# Pixel8x4U.net
KiCad netlist of a schematic drawn in EAGLE
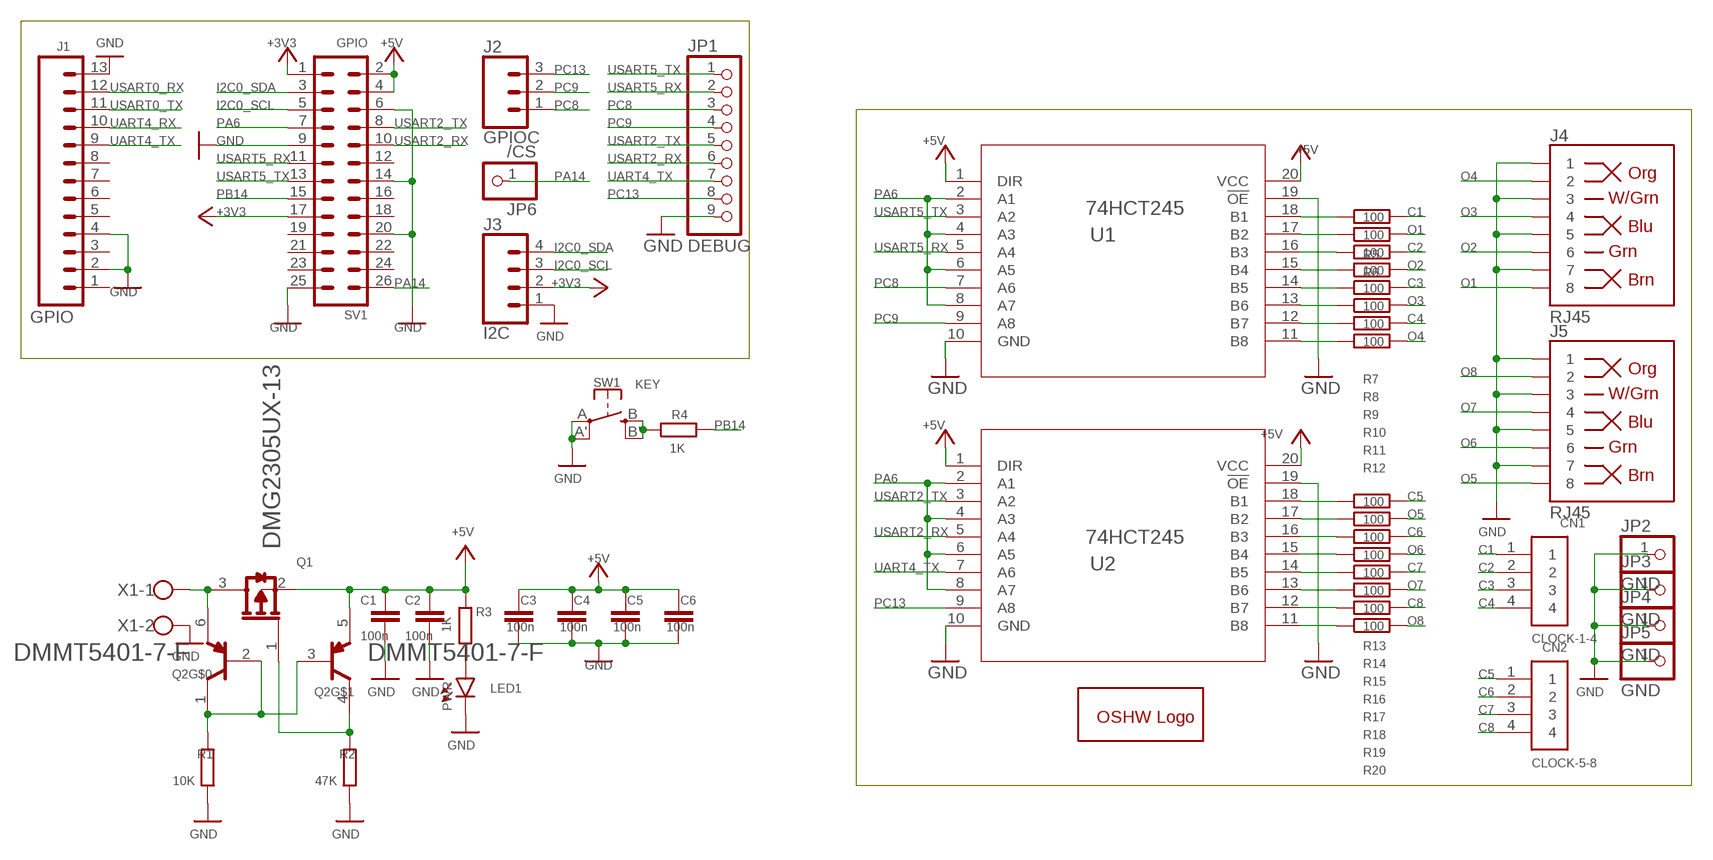
[diagram p0: schematic, sheet 1]

(export (version "E")
  (design (tool "Eeschema 10.0.6"))
  (components
    (comp (ref "C1")
      (value "100n")
      (footprint "eagle-import:C0603")
      (libsource (lib "eagle-import") (part "C-EUC0603"))
    )
    (comp (ref "C2")
      (value "100n")
      (footprint "eagle-import:C0603")
      (libsource (lib "eagle-import") (part "C-EUC0603"))
    )
    (comp (ref "C3")
      (value "100n")
      (footprint "eagle-import:C0603")
      (libsource (lib "eagle-import") (part "C-EUC0603"))
    )
    (comp (ref "C4")
      (value "100n")
      (footprint "eagle-import:C0603")
      (libsource (lib "eagle-import") (part "C-EUC0603"))
    )
    (comp (ref "C5")
      (value "100n")
      (footprint "eagle-import:C0603")
      (libsource (lib "eagle-import") (part "C-EUC0603"))
    )
    (comp (ref "C6")
      (value "100n")
      (footprint "eagle-import:C0603")
      (libsource (lib "eagle-import") (part "C-EUC0603"))
    )
    (comp (ref "CN1")
      (value "CLOCK-1-4")
      (footprint "eagle-import:1X04-CLEANBIG")
      (libsource (lib "eagle-import") (part "1X4-CLEANBIG"))
    )
    (comp (ref "CN2")
      (value "CLOCK-5-8")
      (footprint "eagle-import:1X04-CLEANBIG")
      (libsource (lib "eagle-import") (part "1X4-CLEANBIG"))
    )
    (comp (ref "GOLD_ORB_SM1")
      (value "OSHWLOGOLOGO5MM")
      (footprint "eagle-import:OSHW_5MM")
      (libsource (lib "eagle-import") (part "OSHWLOGOLOGO5MM"))
    )
    (comp (ref "J1")
      (value "GPIO")
      (footprint "eagle-import:1X13")
      (libsource (lib "eagle-import") (part "CONN_13"))
    )
    (comp (ref "J2")
      (value "GPIOC")
      (footprint "eagle-import:1X03")
      (libsource (lib "eagle-import") (part "CONN_03"))
    )
    (comp (ref "J3")
      (value "I2C")
      (footprint "eagle-import:1X04")
      (libsource (lib "eagle-import") (part "CONN_04"))
    )
    (comp (ref "J4")
      (value "RJ45")
      (footprint "eagle-import:RJ45-8")
      (libsource (lib "eagle-import") (part "RJ45-8"))
    )
    (comp (ref "J5")
      (value "RJ45")
      (footprint "eagle-import:RJ45-8")
      (libsource (lib "eagle-import") (part "RJ45-8"))
    )
    (comp (ref "JP1")
      (value "DEBUG")
      (footprint "eagle-import:1X09")
      (libsource (lib "eagle-import") (part "PINHD-1X9"))
    )
    (comp (ref "JP2")
      (value "GND")
      (footprint "eagle-import:1X01-CLEANBIG")
      (libsource (lib "eagle-import") (part "PINHD-1X1CB"))
    )
    (comp (ref "JP3")
      (value "GND")
      (footprint "eagle-import:1X01-CLEANBIG")
      (libsource (lib "eagle-import") (part "PINHD-1X1CB"))
    )
    (comp (ref "JP4")
      (value "GND")
      (footprint "eagle-import:1X01-CLEANBIG")
      (libsource (lib "eagle-import") (part "PINHD-1X1CB"))
    )
    (comp (ref "JP5")
      (value "GND")
      (footprint "eagle-import:1X01-CLEANBIG")
      (libsource (lib "eagle-import") (part "PINHD-1X1CB"))
    )
    (comp (ref "JP6")
      (value "/CS")
      (footprint "eagle-import:1X01-CLEANBIG")
      (libsource (lib "eagle-import") (part "PINHD-1X1CB"))
    )
    (comp (ref "LED1")
      (value "PWR")
      (footprint "eagle-import:CHIP-LED0603")
      (libsource (lib "eagle-import") (part "LEDCHIP-LED0603"))
    )
    (comp (ref "Q1")
      (value "DIODES_INC._DMG2305UX-13DIODES_INC._DMG2305UX-13_0_0")
      (footprint "eagle-import:DIODES_INC._DMG2305UX-13_0")
      (fields
        (field (name "DIGIKEY_PART_NUMBER") "DMG2305UX-13DICT-ND")
        (field (name "MF") "Diodes Inc.")
        (field (name "MOUSER_PART_NUMBER") "621-DMG2305UX-13")
      )
      (libsource (lib "eagle-import") (part "DIODES_INC._DMG2305UX-13DIODES_INC._DMG2305UX-13_0_0"))
    )
    (comp (ref "Q2")
      (value "DMMT5401-7-F_0_0")
      (footprint "eagle-import:DIODES_DMMT5401-7-F_0")
      (fields
        (field (name "DIGIKEY_PART_NUMBER") "DMMT5401-FDICT-ND")
        (field (name "MF") "Diodes")
        (field (name "MOUSER_PART_NUMBER") "621-DMMT5401-7-F")
      )
      (libsource (lib "eagle-import") (part "DIODES_DMMT5401-7-FDIODES_DMMT5401-7-F_0_0"))
    )
    (comp (ref "R1")
      (value "10K")
      (footprint "eagle-import:R0402")
      (libsource (lib "eagle-import") (part "R-EU_R0402"))
    )
    (comp (ref "R2")
      (value "47K")
      (footprint "eagle-import:R0402")
      (libsource (lib "eagle-import") (part "R-EU_R0402"))
    )
    (comp (ref "R3")
      (value "1K")
      (footprint "eagle-import:R0402")
      (libsource (lib "eagle-import") (part "resistor_348_R-EU_R0402"))
    )
    (comp (ref "R4")
      (value "1K")
      (footprint "eagle-import:R0402")
      (libsource (lib "eagle-import") (part "resistor_348_R-EU_R0402"))
    )
    (comp (ref "R5")
      (value "100")
      (footprint "eagle-import:R0402")
      (libsource (lib "eagle-import") (part "R-EU_R0402"))
    )
    (comp (ref "R6")
      (value "100")
      (footprint "eagle-import:R0402")
      (libsource (lib "eagle-import") (part "R-EU_R0402"))
    )
    (comp (ref "R7")
      (value "100")
      (footprint "eagle-import:R0402")
      (libsource (lib "eagle-import") (part "R-EU_R0402"))
    )
    (comp (ref "R8")
      (value "100")
      (footprint "eagle-import:R0402")
      (libsource (lib "eagle-import") (part "R-EU_R0402"))
    )
    (comp (ref "R9")
      (value "100")
      (footprint "eagle-import:R0402")
      (libsource (lib "eagle-import") (part "R-EU_R0402"))
    )
    (comp (ref "R10")
      (value "100")
      (footprint "eagle-import:R0402")
      (libsource (lib "eagle-import") (part "R-EU_R0402"))
    )
    (comp (ref "R11")
      (value "100")
      (footprint "eagle-import:R0402")
      (libsource (lib "eagle-import") (part "R-EU_R0402"))
    )
    (comp (ref "R12")
      (value "100")
      (footprint "eagle-import:R0402")
      (libsource (lib "eagle-import") (part "R-EU_R0402"))
    )
    (comp (ref "R13")
      (value "100")
      (footprint "eagle-import:R0402")
      (libsource (lib "eagle-import") (part "R-EU_R0402"))
    )
    (comp (ref "R14")
      (value "100")
      (footprint "eagle-import:R0402")
      (libsource (lib "eagle-import") (part "R-EU_R0402"))
    )
    (comp (ref "R15")
      (value "100")
      (footprint "eagle-import:R0402")
      (libsource (lib "eagle-import") (part "R-EU_R0402"))
    )
    (comp (ref "R16")
      (value "100")
      (footprint "eagle-import:R0402")
      (libsource (lib "eagle-import") (part "R-EU_R0402"))
    )
    (comp (ref "R17")
      (value "100")
      (footprint "eagle-import:R0402")
      (libsource (lib "eagle-import") (part "R-EU_R0402"))
    )
    (comp (ref "R18")
      (value "100")
      (footprint "eagle-import:R0402")
      (libsource (lib "eagle-import") (part "R-EU_R0402"))
    )
    (comp (ref "R19")
      (value "100")
      (footprint "eagle-import:R0402")
      (libsource (lib "eagle-import") (part "R-EU_R0402"))
    )
    (comp (ref "R20")
      (value "100")
      (footprint "eagle-import:R0402")
      (libsource (lib "eagle-import") (part "R-EU_R0402"))
    )
    (comp (ref "SV1")
      (value "GPIO")
      (footprint "eagle-import:MA13-2")
      (libsource (lib "eagle-import") (part "MA13-2"))
    )
    (comp (ref "SW1")
      (value "KEY")
      (footprint "eagle-import:EVQ-Q2")
      (libsource (lib "eagle-import") (part "SPST_TACT-EVQQ2"))
    )
    (comp (ref "U1")
      (value "74HCT245")
      (footprint "eagle-import:PW20")
      (fields
        (field (name "GENERIC_PART_NUMBER") "SN74HCT245")
        (field (name "MANUFACTURER") "Texas Instruments")
        (field (name "MANUFACTURER_PART_NUMBER") "SN74HCT245PWR")
      )
      (libsource (lib "eagle-import") (part "SN74HCT245PWR"))
    )
    (comp (ref "U2")
      (value "74HCT245")
      (footprint "eagle-import:PW20")
      (fields
        (field (name "GENERIC_PART_NUMBER") "SN74HCT245")
        (field (name "MANUFACTURER") "Texas Instruments")
        (field (name "MANUFACTURER_PART_NUMBER") "SN74HCT245PWR")
      )
      (libsource (lib "eagle-import") (part "SN74HCT245PWR"))
    )
    (comp (ref "X1")
      (value "W237-102")
      (footprint "eagle-import:W237-102")
      (fields (field (name "MPN") "237-102"))
      (libsource (lib "eagle-import") (part "W237-102"))
    )
  )
  (nets
    (net (code "1") (name "+3V3") (class "Default")
      (node (ref "J3") (pin "2") (pinfunction "2_2") (pintype "passive"))
      (node (ref "SV1") (pin "1") (pinfunction "1_1") (pintype "passive"))
      (node (ref "SV1") (pin "17") (pinfunction "17_17") (pintype "passive"))
    )
    (net (code "2") (name "+5V") (class "Default")
      (node (ref "C1") (pin "1") (pinfunction "1_1") (pintype "passive"))
      (node (ref "C2") (pin "1") (pinfunction "1_1") (pintype "passive"))
      (node (ref "C3") (pin "1") (pinfunction "1_1") (pintype "passive"))
      (node (ref "C4") (pin "1") (pinfunction "1_1") (pintype "passive"))
      (node (ref "C5") (pin "1") (pinfunction "1_1") (pintype "passive"))
      (node (ref "C6") (pin "1") (pinfunction "1_1") (pintype "passive"))
      (node (ref "Q1") (pin "2") (pinfunction "S_2") (pintype "passive"))
      (node (ref "Q2") (pin "5") (pinfunction "E2_5") (pintype "passive"))
      (node (ref "R3") (pin "1") (pinfunction "1_1") (pintype "passive"))
      (node (ref "SV1") (pin "2") (pinfunction "2_2") (pintype "passive"))
      (node (ref "SV1") (pin "4") (pinfunction "4_4") (pintype "passive"))
      (node (ref "U1") (pin "1") (pinfunction "DIR_1") (pintype "input"))
      (node (ref "U1") (pin "20") (pinfunction "VCC_20") (pintype "power_in"))
      (node (ref "U2") (pin "1") (pinfunction "DIR_1") (pintype "input"))
      (node (ref "U2") (pin "20") (pinfunction "VCC_20") (pintype "power_in"))
    )
    (net (code "3") (name "/C1") (class "Default")
      (node (ref "CN1") (pin "1") (pinfunction "1_1") (pintype "bidirectional"))
      (node (ref "R5") (pin "2") (pinfunction "2_2") (pintype "passive"))
    )
    (net (code "4") (name "/C2") (class "Default")
      (node (ref "CN1") (pin "2") (pinfunction "2_2") (pintype "bidirectional"))
      (node (ref "R7") (pin "2") (pinfunction "2_2") (pintype "passive"))
    )
    (net (code "5") (name "/C3") (class "Default")
      (node (ref "CN1") (pin "3") (pinfunction "3_3") (pintype "bidirectional"))
      (node (ref "R9") (pin "2") (pinfunction "2_2") (pintype "passive"))
    )
    (net (code "6") (name "/C4") (class "Default")
      (node (ref "CN1") (pin "4") (pinfunction "4_4") (pintype "bidirectional"))
      (node (ref "R11") (pin "2") (pinfunction "2_2") (pintype "passive"))
    )
    (net (code "7") (name "/C5") (class "Default")
      (node (ref "CN2") (pin "1") (pinfunction "1_1") (pintype "bidirectional"))
      (node (ref "R13") (pin "2") (pinfunction "2_2") (pintype "passive"))
    )
    (net (code "8") (name "/C6") (class "Default")
      (node (ref "CN2") (pin "2") (pinfunction "2_2") (pintype "bidirectional"))
      (node (ref "R15") (pin "2") (pinfunction "2_2") (pintype "passive"))
    )
    (net (code "9") (name "/C7") (class "Default")
      (node (ref "CN2") (pin "3") (pinfunction "3_3") (pintype "bidirectional"))
      (node (ref "R17") (pin "2") (pinfunction "2_2") (pintype "passive"))
    )
    (net (code "10") (name "/C8") (class "Default")
      (node (ref "CN2") (pin "4") (pinfunction "4_4") (pintype "bidirectional"))
      (node (ref "R19") (pin "2") (pinfunction "2_2") (pintype "passive"))
    )
    (net (code "11") (name "/I2C0_SCL") (class "Default")
      (node (ref "J3") (pin "3") (pinfunction "3_3") (pintype "passive"))
      (node (ref "SV1") (pin "5") (pinfunction "5_5") (pintype "passive"))
    )
    (net (code "12") (name "/I2C0_SDA") (class "Default")
      (node (ref "J3") (pin "4") (pinfunction "4_4") (pintype "passive"))
      (node (ref "SV1") (pin "3") (pinfunction "3_3") (pintype "passive"))
    )
    (net (code "13") (name "/O1") (class "Default")
      (node (ref "J4") (pin "8") (pinfunction "8_8") (pintype "bidirectional"))
      (node (ref "R6") (pin "2") (pinfunction "2_2") (pintype "passive"))
    )
    (net (code "14") (name "/O2") (class "Default")
      (node (ref "J4") (pin "6") (pinfunction "6_6") (pintype "bidirectional"))
      (node (ref "R8") (pin "2") (pinfunction "2_2") (pintype "passive"))
    )
    (net (code "15") (name "/O3") (class "Default")
      (node (ref "J4") (pin "4") (pinfunction "4_4") (pintype "bidirectional"))
      (node (ref "R10") (pin "2") (pinfunction "2_2") (pintype "passive"))
    )
    (net (code "16") (name "/O4") (class "Default")
      (node (ref "J4") (pin "2") (pinfunction "2_2") (pintype "bidirectional"))
      (node (ref "R12") (pin "2") (pinfunction "2_2") (pintype "passive"))
    )
    (net (code "17") (name "/O5") (class "Default")
      (node (ref "J5") (pin "8") (pinfunction "8_8") (pintype "bidirectional"))
      (node (ref "R14") (pin "2") (pinfunction "2_2") (pintype "passive"))
    )
    (net (code "18") (name "/O6") (class "Default")
      (node (ref "J5") (pin "6") (pinfunction "6_6") (pintype "bidirectional"))
      (node (ref "R16") (pin "2") (pinfunction "2_2") (pintype "passive"))
    )
    (net (code "19") (name "/O7") (class "Default")
      (node (ref "J5") (pin "4") (pinfunction "4_4") (pintype "bidirectional"))
      (node (ref "R18") (pin "2") (pinfunction "2_2") (pintype "passive"))
    )
    (net (code "20") (name "/O8") (class "Default")
      (node (ref "J5") (pin "2") (pinfunction "2_2") (pintype "bidirectional"))
      (node (ref "R20") (pin "2") (pinfunction "2_2") (pintype "passive"))
    )
    (net (code "21") (name "/PA6") (class "Default")
      (node (ref "SV1") (pin "7") (pinfunction "7_7") (pintype "passive"))
      (node (ref "U1") (pin "2") (pinfunction "A1_2") (pintype "bidirectional"))
      (node (ref "U1") (pin "4") (pinfunction "A3_4") (pintype "bidirectional"))
      (node (ref "U1") (pin "6") (pinfunction "A5_6") (pintype "bidirectional"))
      (node (ref "U1") (pin "8") (pinfunction "A7_8") (pintype "bidirectional"))
      (node (ref "U2") (pin "2") (pinfunction "A1_2") (pintype "bidirectional"))
      (node (ref "U2") (pin "4") (pinfunction "A3_4") (pintype "bidirectional"))
      (node (ref "U2") (pin "6") (pinfunction "A5_6") (pintype "bidirectional"))
      (node (ref "U2") (pin "8") (pinfunction "A7_8") (pintype "bidirectional"))
    )
    (net (code "22") (name "/PA14") (class "Default")
      (node (ref "JP6") (pin "1") (pinfunction "1_1") (pintype "passive"))
      (node (ref "SV1") (pin "26") (pinfunction "26_26") (pintype "passive"))
    )
    (net (code "23") (name "/PB14") (class "Default")
      (node (ref "R4") (pin "2") (pinfunction "2_2") (pintype "passive"))
      (node (ref "SV1") (pin "15") (pinfunction "15_15") (pintype "passive"))
    )
    (net (code "24") (name "/PC8") (class "Default")
      (node (ref "J2") (pin "1") (pinfunction "1_1") (pintype "passive"))
      (node (ref "JP1") (pin "3") (pinfunction "3_3") (pintype "passive"))
      (node (ref "U1") (pin "7") (pinfunction "A6_7") (pintype "bidirectional"))
    )
    (net (code "25") (name "/PC9") (class "Default")
      (node (ref "J2") (pin "2") (pinfunction "2_2") (pintype "passive"))
      (node (ref "JP1") (pin "4") (pinfunction "4_4") (pintype "passive"))
      (node (ref "U1") (pin "9") (pinfunction "A8_9") (pintype "bidirectional"))
    )
    (net (code "26") (name "/PC13") (class "Default")
      (node (ref "J2") (pin "3") (pinfunction "3_3") (pintype "passive"))
      (node (ref "JP1") (pin "8") (pinfunction "8_8") (pintype "passive"))
      (node (ref "U2") (pin "9") (pinfunction "A8_9") (pintype "bidirectional"))
    )
    (net (code "27") (name "/UART4_RX") (class "Default")
      (node (ref "J1") (pin "10") (pinfunction "10_10") (pintype "passive"))
    )
    (net (code "28") (name "/UART4_TX") (class "Default")
      (node (ref "J1") (pin "9") (pinfunction "9_9") (pintype "passive"))
      (node (ref "JP1") (pin "7") (pinfunction "7_7") (pintype "passive"))
      (node (ref "U2") (pin "7") (pinfunction "A6_7") (pintype "bidirectional"))
    )
    (net (code "29") (name "/USART0_RX") (class "Default")
      (node (ref "J1") (pin "12") (pinfunction "12_12") (pintype "passive"))
    )
    (net (code "30") (name "/USART0_TX") (class "Default")
      (node (ref "J1") (pin "11") (pinfunction "11_11") (pintype "passive"))
    )
    (net (code "31") (name "/USART2_RX") (class "Default")
      (node (ref "JP1") (pin "6") (pinfunction "6_6") (pintype "passive"))
      (node (ref "SV1") (pin "10") (pinfunction "10_10") (pintype "passive"))
      (node (ref "U2") (pin "5") (pinfunction "A4_5") (pintype "bidirectional"))
    )
    (net (code "32") (name "/USART2_TX") (class "Default")
      (node (ref "JP1") (pin "5") (pinfunction "5_5") (pintype "passive"))
      (node (ref "SV1") (pin "8") (pinfunction "8_8") (pintype "passive"))
      (node (ref "U2") (pin "3") (pinfunction "A2_3") (pintype "bidirectional"))
    )
    (net (code "33") (name "/USART5_RX") (class "Default")
      (node (ref "JP1") (pin "2") (pinfunction "2_2") (pintype "passive"))
      (node (ref "SV1") (pin "11") (pinfunction "11_11") (pintype "passive"))
      (node (ref "U1") (pin "5") (pinfunction "A4_5") (pintype "bidirectional"))
    )
    (net (code "34") (name "/USART5_TX") (class "Default")
      (node (ref "JP1") (pin "1") (pinfunction "1_1") (pintype "passive"))
      (node (ref "SV1") (pin "13") (pinfunction "13_13") (pintype "passive"))
      (node (ref "U1") (pin "3") (pinfunction "A2_3") (pintype "bidirectional"))
    )
    (net (code "35") (name "GND") (class "Default")
      (node (ref "C1") (pin "2") (pinfunction "2_2") (pintype "passive"))
      (node (ref "C2") (pin "2") (pinfunction "2_2") (pintype "passive"))
      (node (ref "C3") (pin "2") (pinfunction "2_2") (pintype "passive"))
      (node (ref "C4") (pin "2") (pinfunction "2_2") (pintype "passive"))
      (node (ref "C5") (pin "2") (pinfunction "2_2") (pintype "passive"))
      (node (ref "C6") (pin "2") (pinfunction "2_2") (pintype "passive"))
      (node (ref "J1") (pin "13") (pinfunction "13_13") (pintype "passive"))
      (node (ref "J1") (pin "2") (pinfunction "2_2") (pintype "passive"))
      (node (ref "J1") (pin "4") (pinfunction "4_4") (pintype "passive"))
      (node (ref "J3") (pin "1") (pinfunction "1_1") (pintype "passive"))
      (node (ref "J4") (pin "1") (pinfunction "1_1") (pintype "bidirectional"))
      (node (ref "J4") (pin "3") (pinfunction "3_3") (pintype "bidirectional"))
      (node (ref "J4") (pin "5") (pinfunction "5_5") (pintype "bidirectional"))
      (node (ref "J4") (pin "7") (pinfunction "7_7") (pintype "bidirectional"))
      (node (ref "J5") (pin "1") (pinfunction "1_1") (pintype "bidirectional"))
      (node (ref "J5") (pin "3") (pinfunction "3_3") (pintype "bidirectional"))
      (node (ref "J5") (pin "5") (pinfunction "5_5") (pintype "bidirectional"))
      (node (ref "J5") (pin "7") (pinfunction "7_7") (pintype "bidirectional"))
      (node (ref "JP1") (pin "9") (pinfunction "9_9") (pintype "passive"))
      (node (ref "JP2") (pin "1") (pinfunction "1_1") (pintype "passive"))
      (node (ref "JP3") (pin "1") (pinfunction "1_1") (pintype "passive"))
      (node (ref "JP4") (pin "1") (pinfunction "1_1") (pintype "passive"))
      (node (ref "JP5") (pin "1") (pinfunction "1_1") (pintype "passive"))
      (node (ref "LED1") (pin "C") (pinfunction "C_C") (pintype "passive"))
      (node (ref "R1") (pin "1") (pinfunction "1_1") (pintype "passive"))
      (node (ref "R2") (pin "1") (pinfunction "1_1") (pintype "passive"))
      (node (ref "SV1") (pin "14") (pinfunction "14_14") (pintype "passive"))
      (node (ref "SV1") (pin "20") (pinfunction "20_20") (pintype "passive"))
      (node (ref "SV1") (pin "25") (pinfunction "25_25") (pintype "passive"))
      (node (ref "SV1") (pin "6") (pinfunction "6_6") (pintype "passive"))
      (node (ref "SV1") (pin "9") (pinfunction "9_9") (pintype "passive"))
      (node (ref "SW1") (pin "A") (pinfunction "P_A") (pintype "passive"))
      (node (ref "SW1") (pin "A'") (pinfunction "P1_A'") (pintype "passive"))
      (node (ref "U1") (pin "10") (pinfunction "GND_10") (pintype "power_in"))
      (node (ref "U1") (pin "19") (pinfunction "~{OE}_19") (pintype "input"))
      (node (ref "U2") (pin "10") (pinfunction "GND_10") (pintype "power_in"))
      (node (ref "U2") (pin "19") (pinfunction "~{OE}_19") (pintype "input"))
      (node (ref "X1") (pin "2") (pinfunction "KL_2") (pintype "passive"))
    )
    (net (code "36") (name "Net-(LED1-PadA)") (class "Default")
      (node (ref "LED1") (pin "A") (pinfunction "A_A") (pintype "passive"))
      (node (ref "R3") (pin "2") (pinfunction "2_2") (pintype "passive"))
    )
    (net (code "37") (name "Net-(Q1-D)") (class "Default")
      (node (ref "Q1") (pin "3") (pinfunction "D_3") (pintype "passive"))
      (node (ref "Q2") (pin "6") (pinfunction "E1_6") (pintype "passive"))
      (node (ref "X1") (pin "1") (pinfunction "KL_1") (pintype "passive"))
    )
    (net (code "38") (name "Net-(Q1-G)") (class "Default")
      (node (ref "Q1") (pin "1") (pinfunction "G_1") (pintype "passive"))
      (node (ref "Q2") (pin "4") (pinfunction "C2_4") (pintype "passive"))
      (node (ref "R2") (pin "2") (pinfunction "2_2") (pintype "passive"))
    )
    (net (code "39") (name "Net-(Q2A-B1)") (class "Default")
      (node (ref "Q2") (pin "1") (pinfunction "C1_1") (pintype "passive"))
      (node (ref "Q2") (pin "2") (pinfunction "B1_2") (pintype "passive"))
      (node (ref "Q2") (pin "3") (pinfunction "B2_3") (pintype "passive"))
      (node (ref "R1") (pin "2") (pinfunction "2_2") (pintype "passive"))
    )
    (net (code "40") (name "Net-(SW1-S)") (class "Default")
      (node (ref "R4") (pin "1") (pinfunction "1_1") (pintype "passive"))
      (node (ref "SW1") (pin "B") (pinfunction "S_B") (pintype "passive"))
      (node (ref "SW1") (pin "B'") (pinfunction "S1_B'") (pintype "passive"))
    )
    (net (code "41") (name "Net-(U1-B1)") (class "Default")
      (node (ref "R5") (pin "1") (pinfunction "1_1") (pintype "passive"))
      (node (ref "U1") (pin "18") (pinfunction "B1_18") (pintype "bidirectional"))
    )
    (net (code "42") (name "Net-(U1-B2)") (class "Default")
      (node (ref "R6") (pin "1") (pinfunction "1_1") (pintype "passive"))
      (node (ref "U1") (pin "17") (pinfunction "B2_17") (pintype "bidirectional"))
    )
    (net (code "43") (name "Net-(U1-B3)") (class "Default")
      (node (ref "R7") (pin "1") (pinfunction "1_1") (pintype "passive"))
      (node (ref "U1") (pin "16") (pinfunction "B3_16") (pintype "bidirectional"))
    )
    (net (code "44") (name "Net-(U1-B4)") (class "Default")
      (node (ref "R8") (pin "1") (pinfunction "1_1") (pintype "passive"))
      (node (ref "U1") (pin "15") (pinfunction "B4_15") (pintype "bidirectional"))
    )
    (net (code "45") (name "Net-(U1-B5)") (class "Default")
      (node (ref "R9") (pin "1") (pinfunction "1_1") (pintype "passive"))
      (node (ref "U1") (pin "14") (pinfunction "B5_14") (pintype "bidirectional"))
    )
    (net (code "46") (name "Net-(U1-B6)") (class "Default")
      (node (ref "R10") (pin "1") (pinfunction "1_1") (pintype "passive"))
      (node (ref "U1") (pin "13") (pinfunction "B6_13") (pintype "bidirectional"))
    )
    (net (code "47") (name "Net-(U1-B7)") (class "Default")
      (node (ref "R11") (pin "1") (pinfunction "1_1") (pintype "passive"))
      (node (ref "U1") (pin "12") (pinfunction "B7_12") (pintype "bidirectional"))
    )
    (net (code "48") (name "Net-(U1-B8)") (class "Default")
      (node (ref "R12") (pin "1") (pinfunction "1_1") (pintype "passive"))
      (node (ref "U1") (pin "11") (pinfunction "B8_11") (pintype "bidirectional"))
    )
    (net (code "49") (name "Net-(U2-B1)") (class "Default")
      (node (ref "R13") (pin "1") (pinfunction "1_1") (pintype "passive"))
      (node (ref "U2") (pin "18") (pinfunction "B1_18") (pintype "bidirectional"))
    )
    (net (code "50") (name "Net-(U2-B2)") (class "Default")
      (node (ref "R14") (pin "1") (pinfunction "1_1") (pintype "passive"))
      (node (ref "U2") (pin "17") (pinfunction "B2_17") (pintype "bidirectional"))
    )
    (net (code "51") (name "Net-(U2-B3)") (class "Default")
      (node (ref "R15") (pin "1") (pinfunction "1_1") (pintype "passive"))
      (node (ref "U2") (pin "16") (pinfunction "B3_16") (pintype "bidirectional"))
    )
    (net (code "52") (name "Net-(U2-B4)") (class "Default")
      (node (ref "R16") (pin "1") (pinfunction "1_1") (pintype "passive"))
      (node (ref "U2") (pin "15") (pinfunction "B4_15") (pintype "bidirectional"))
    )
    (net (code "53") (name "Net-(U2-B5)") (class "Default")
      (node (ref "R17") (pin "1") (pinfunction "1_1") (pintype "passive"))
      (node (ref "U2") (pin "14") (pinfunction "B5_14") (pintype "bidirectional"))
    )
    (net (code "54") (name "Net-(U2-B6)") (class "Default")
      (node (ref "R18") (pin "1") (pinfunction "1_1") (pintype "passive"))
      (node (ref "U2") (pin "13") (pinfunction "B6_13") (pintype "bidirectional"))
    )
    (net (code "55") (name "Net-(U2-B7)") (class "Default")
      (node (ref "R19") (pin "1") (pinfunction "1_1") (pintype "passive"))
      (node (ref "U2") (pin "12") (pinfunction "B7_12") (pintype "bidirectional"))
    )
    (net (code "56") (name "Net-(U2-B8)") (class "Default")
      (node (ref "R20") (pin "1") (pinfunction "1_1") (pintype "passive"))
      (node (ref "U2") (pin "11") (pinfunction "B8_11") (pintype "bidirectional"))
    )
    (net (code "57") (name "unconnected-(J1-Pad1)") (class "Default")
      (node (ref "J1") (pin "1") (pinfunction "1_1") (pintype "passive"))
    )
    (net (code "58") (name "unconnected-(J1-Pad3)") (class "Default")
      (node (ref "J1") (pin "3") (pinfunction "3_3") (pintype "passive"))
    )
    (net (code "59") (name "unconnected-(J1-Pad5)") (class "Default")
      (node (ref "J1") (pin "5") (pinfunction "5_5") (pintype "passive"))
    )
    (net (code "60") (name "unconnected-(J1-Pad6)") (class "Default")
      (node (ref "J1") (pin "6") (pinfunction "6_6") (pintype "passive"))
    )
    (net (code "61") (name "unconnected-(J1-Pad7)") (class "Default")
      (node (ref "J1") (pin "7") (pinfunction "7_7") (pintype "passive"))
    )
    (net (code "62") (name "unconnected-(J1-Pad8)") (class "Default")
      (node (ref "J1") (pin "8") (pinfunction "8_8") (pintype "passive"))
    )
    (net (code "63") (name "unconnected-(SV1-Pad12)") (class "Default")
      (node (ref "SV1") (pin "12") (pinfunction "12_12") (pintype "passive"))
    )
    (net (code "64") (name "unconnected-(SV1-Pad16)") (class "Default")
      (node (ref "SV1") (pin "16") (pinfunction "16_16") (pintype "passive"))
    )
    (net (code "65") (name "unconnected-(SV1-Pad18)") (class "Default")
      (node (ref "SV1") (pin "18") (pinfunction "18_18") (pintype "passive"))
    )
    (net (code "66") (name "unconnected-(SV1-Pad19)") (class "Default")
      (node (ref "SV1") (pin "19") (pinfunction "19_19") (pintype "passive"))
    )
    (net (code "67") (name "unconnected-(SV1-Pad21)") (class "Default")
      (node (ref "SV1") (pin "21") (pinfunction "21_21") (pintype "passive"))
    )
    (net (code "68") (name "unconnected-(SV1-Pad22)") (class "Default")
      (node (ref "SV1") (pin "22") (pinfunction "22_22") (pintype "passive"))
    )
    (net (code "69") (name "unconnected-(SV1-Pad23)") (class "Default")
      (node (ref "SV1") (pin "23") (pinfunction "23_23") (pintype "passive"))
    )
    (net (code "70") (name "unconnected-(SV1-Pad24)") (class "Default")
      (node (ref "SV1") (pin "24") (pinfunction "24_24") (pintype "passive"))
    )
  )
)
